# Bulb.net
KiCad netlist of a schematic drawn in Altium Designer
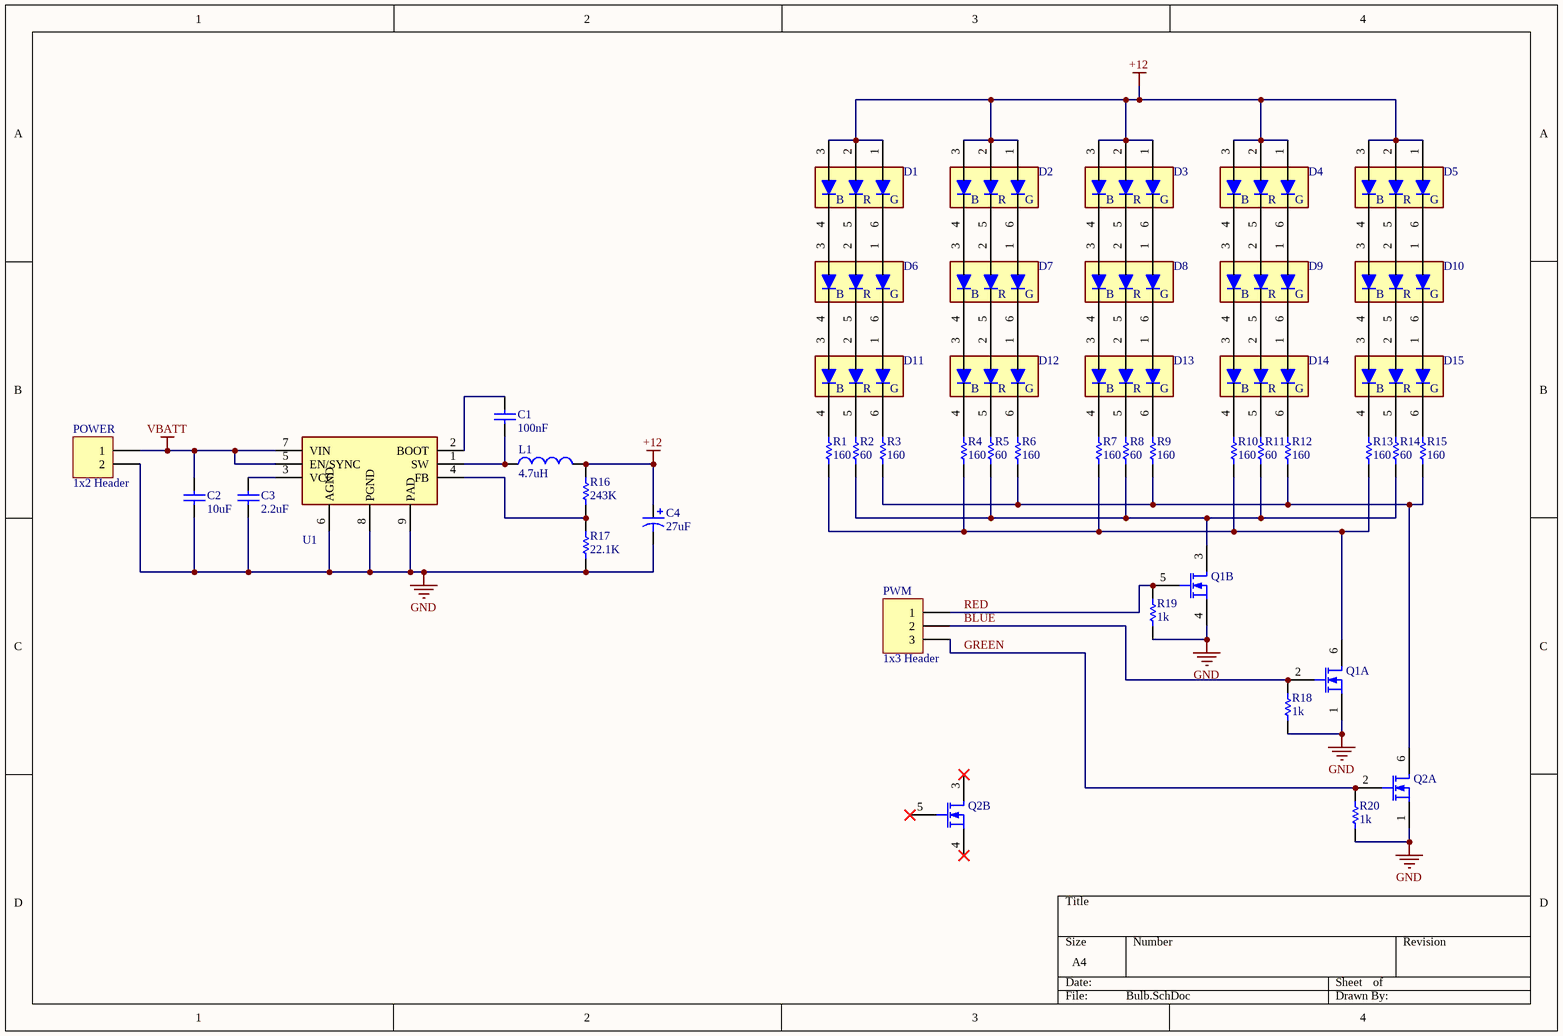
[diagram p0: Bulb.SchDoc]

(export (version "E")
  (design (tool "Eeschema 10.0.6"))
  (components
    (comp (ref "C1")
      (value "100nF")
      (footprint "0603 - Capacitor")
      (description "Nonpolarized Capacitor")
      (fields
        (field (name "MANUFACTURER") "Murata")
        (field (name "MANUFACTURER PART NUMBER") "GRM155R71C104KA88D")
      )
      (libsource (lib "General") (part "Capacitor - Nonpolarized"))
    )
    (comp (ref "C2")
      (value "10uF")
      (footprint "0603 - Capacitor")
      (description "Nonpolarized Capacitor")
      (fields
        (field (name "MANUFACTURER") "TDK")
        (field (name "MANUFACTURER PART NUMBER") "C3225X7R1H106M250AC")
      )
      (libsource (lib "General") (part "Capacitor - Nonpolarized"))
    )
    (comp (ref "C3")
      (value "2.2uF")
      (footprint "0603 - Capacitor")
      (description "Nonpolarized Capacitor")
      (fields
        (field (name "MANUFACTURER") "Kemet")
        (field (name "MANUFACTURER PART NUMBER") "C0603C225K8PACTU")
      )
      (libsource (lib "General") (part "Capacitor - Nonpolarized"))
    )
    (comp (ref "C4")
      (value "27uF")
      (footprint "OCVZ0606 - CAPACITOR")
      (description "Polarized Capacitor")
      (fields
        (field (name "MANUFACTURER") "Panasonic Electronic Components")
        (field (name "MANUFACTURER PART NUMBER") "EEE-FK1E270SR")
      )
      (libsource (lib "General") (part "Capacitor - Polarized"))
    )
    (comp (ref "D1")
      (value "RGB LED- Indiv")
      (footprint "RGB-6")
      (description "6-pin RGB LED")
      (fields
        (field (name "MANUFACTURER PART NUMBER") "HL-AF-5060H271BU46FU79GC-S1-THL")
        (field (name "MANUFACTURER") "Hongli Zhihui (HONGLITRONIC)")
      )
      (libsource (lib "General") (part "RGB LED- Indiv"))
    )
    (comp (ref "D2")
      (value "RGB LED- Indiv")
      (footprint "RGB-6")
      (description "6-pin RGB LED")
      (fields
        (field (name "MANUFACTURER PART NUMBER") "HL-AF-5060H271BU46FU79GC-S1-THL")
        (field (name "MANUFACTURER") "Hongli Zhihui (HONGLITRONIC)")
      )
      (libsource (lib "General") (part "RGB LED- Indiv"))
    )
    (comp (ref "D3")
      (value "RGB LED- Indiv")
      (footprint "RGB-6")
      (description "6-pin RGB LED")
      (fields
        (field (name "MANUFACTURER PART NUMBER") "HL-AF-5060H271BU46FU79GC-S1-THL")
        (field (name "MANUFACTURER") "Hongli Zhihui (HONGLITRONIC)")
      )
      (libsource (lib "General") (part "RGB LED- Indiv"))
    )
    (comp (ref "D4")
      (value "RGB LED- Indiv")
      (footprint "RGB-6")
      (description "6-pin RGB LED")
      (fields
        (field (name "MANUFACTURER PART NUMBER") "HL-AF-5060H271BU46FU79GC-S1-THL")
        (field (name "MANUFACTURER") "Hongli Zhihui (HONGLITRONIC)")
      )
      (libsource (lib "General") (part "RGB LED- Indiv"))
    )
    (comp (ref "D5")
      (value "RGB LED- Indiv")
      (footprint "RGB-6")
      (description "6-pin RGB LED")
      (fields
        (field (name "MANUFACTURER PART NUMBER") "HL-AF-5060H271BU46FU79GC-S1-THL")
        (field (name "MANUFACTURER") "Hongli Zhihui (HONGLITRONIC)")
      )
      (libsource (lib "General") (part "RGB LED- Indiv"))
    )
    (comp (ref "D6")
      (value "RGB LED- Indiv")
      (footprint "RGB-6")
      (description "6-pin RGB LED")
      (fields
        (field (name "MANUFACTURER PART NUMBER") "HL-AF-5060H271BU46FU79GC-S1-THL")
        (field (name "MANUFACTURER") "Hongli Zhihui (HONGLITRONIC)")
      )
      (libsource (lib "General") (part "RGB LED- Indiv"))
    )
    (comp (ref "D7")
      (value "RGB LED- Indiv")
      (footprint "RGB-6")
      (description "6-pin RGB LED")
      (fields
        (field (name "MANUFACTURER PART NUMBER") "HL-AF-5060H271BU46FU79GC-S1-THL")
        (field (name "MANUFACTURER") "Hongli Zhihui (HONGLITRONIC)")
      )
      (libsource (lib "General") (part "RGB LED- Indiv"))
    )
    (comp (ref "D8")
      (value "RGB LED- Indiv")
      (footprint "RGB-6")
      (description "6-pin RGB LED")
      (fields
        (field (name "MANUFACTURER PART NUMBER") "HL-AF-5060H271BU46FU79GC-S1-THL")
        (field (name "MANUFACTURER") "Hongli Zhihui (HONGLITRONIC)")
      )
      (libsource (lib "General") (part "RGB LED- Indiv"))
    )
    (comp (ref "D9")
      (value "RGB LED- Indiv")
      (footprint "RGB-6")
      (description "6-pin RGB LED")
      (fields
        (field (name "MANUFACTURER PART NUMBER") "HL-AF-5060H271BU46FU79GC-S1-THL")
        (field (name "MANUFACTURER") "Hongli Zhihui (HONGLITRONIC)")
      )
      (libsource (lib "General") (part "RGB LED- Indiv"))
    )
    (comp (ref "D10")
      (value "RGB LED- Indiv")
      (footprint "RGB-6")
      (description "6-pin RGB LED")
      (fields
        (field (name "MANUFACTURER PART NUMBER") "HL-AF-5060H271BU46FU79GC-S1-THL")
        (field (name "MANUFACTURER") "Hongli Zhihui (HONGLITRONIC)")
      )
      (libsource (lib "General") (part "RGB LED- Indiv"))
    )
    (comp (ref "D11")
      (value "RGB LED- Indiv")
      (footprint "RGB-6")
      (description "6-pin RGB LED")
      (fields
        (field (name "MANUFACTURER PART NUMBER") "HL-AF-5060H271BU46FU79GC-S1-THL")
        (field (name "MANUFACTURER") "Hongli Zhihui (HONGLITRONIC)")
      )
      (libsource (lib "General") (part "RGB LED- Indiv"))
    )
    (comp (ref "D12")
      (value "RGB LED- Indiv")
      (footprint "RGB-6")
      (description "6-pin RGB LED")
      (fields
        (field (name "MANUFACTURER PART NUMBER") "HL-AF-5060H271BU46FU79GC-S1-THL")
        (field (name "MANUFACTURER") "Hongli Zhihui (HONGLITRONIC)")
      )
      (libsource (lib "General") (part "RGB LED- Indiv"))
    )
    (comp (ref "D13")
      (value "RGB LED- Indiv")
      (footprint "RGB-6")
      (description "6-pin RGB LED")
      (fields
        (field (name "MANUFACTURER PART NUMBER") "HL-AF-5060H271BU46FU79GC-S1-THL")
        (field (name "MANUFACTURER") "Hongli Zhihui (HONGLITRONIC)")
      )
      (libsource (lib "General") (part "RGB LED- Indiv"))
    )
    (comp (ref "D14")
      (value "RGB LED- Indiv")
      (footprint "RGB-6")
      (description "6-pin RGB LED")
      (fields
        (field (name "MANUFACTURER PART NUMBER") "HL-AF-5060H271BU46FU79GC-S1-THL")
        (field (name "MANUFACTURER") "Hongli Zhihui (HONGLITRONIC)")
      )
      (libsource (lib "General") (part "RGB LED- Indiv"))
    )
    (comp (ref "D15")
      (value "RGB LED- Indiv")
      (footprint "RGB-6")
      (description "6-pin RGB LED")
      (fields
        (field (name "MANUFACTURER PART NUMBER") "HL-AF-5060H271BU46FU79GC-S1-THL")
        (field (name "MANUFACTURER") "Hongli Zhihui (HONGLITRONIC)")
      )
      (libsource (lib "General") (part "RGB LED- Indiv"))
    )
    (comp (ref "L1")
      (value "4.7uH")
      (footprint "PA4340 - Inductor")
      (description "Inductor")
      (fields
        (field (name "MANUFACTURER PART NUMBER") "7447706047")
        (field (name "MANUFACTURER") "Würth Elektronik")
      )
      (libsource (lib "General") (part "Inductor"))
    )
    (comp (ref "POWER")
      (value "1x2 Header")
      (footprint "B2B-XH")
      (description "1x2 Pin Header")
      (libsource (lib "GeneralConnectors") (part "1x2 Header"))
    )
    (comp (ref "PWM")
      (value "1x3 Header")
      (footprint "B3B-XH")
      (description "1x3 Pin Header")
      (libsource (lib "GeneralConnectors") (part "1x3 Header"))
    )
    (comp (ref "Q1")
      (value "BSD235NH6327XTSA1")
      (footprint "BSD235NH6327XTSA1")
      (fields (field (name "MANUFACTURER") " Infineon"))
      (libsource (lib "General") (part "BSD235NH6327XTSA1"))
    )
    (comp (ref "Q2")
      (value "BSD235NH6327XTSA1")
      (footprint "BSD235NH6327XTSA1")
      (fields (field (name "MANUFACTURER") " Infineon"))
      (libsource (lib "General") (part "BSD235NH6327XTSA1"))
    )
    (comp (ref "R1")
      (value "160")
      (footprint "1206 - Resistor")
      (description "Resistor")
      (fields (field (name "MANUFACTURER PART NUMBER") "ESR18EZPJ161") (field (name "MANUFACTURER") "Yageo"))
      (libsource (lib "General") (part "Resistor"))
    )
    (comp (ref "R2")
      (value "60")
      (footprint "0603 - Resistor")
      (description "Resistor")
      (fields
        (field (name "MANUFACTURER PART NUMBER") "RC0603FR-0759RL")
        (field (name "MANUFACTURER") "Yageo")
      )
      (libsource (lib "General") (part "Resistor"))
    )
    (comp (ref "R3")
      (value "160")
      (footprint "1206 - Resistor")
      (description "Resistor")
      (fields (field (name "MANUFACTURER PART NUMBER") "ESR18EZPJ161") (field (name "MANUFACTURER") "Yageo"))
      (libsource (lib "General") (part "Resistor"))
    )
    (comp (ref "R4")
      (value "160")
      (footprint "1206 - Resistor")
      (description "Resistor")
      (fields (field (name "MANUFACTURER PART NUMBER") "ESR18EZPJ161") (field (name "MANUFACTURER") "Yageo"))
      (libsource (lib "General") (part "Resistor"))
    )
    (comp (ref "R5")
      (value "60")
      (footprint "0603 - Resistor")
      (description "Resistor")
      (fields
        (field (name "MANUFACTURER PART NUMBER") "RC0603FR-0759RL")
        (field (name "MANUFACTURER") "Yageo")
      )
      (libsource (lib "General") (part "Resistor"))
    )
    (comp (ref "R6")
      (value "160")
      (footprint "1206 - Resistor")
      (description "Resistor")
      (fields (field (name "MANUFACTURER PART NUMBER") "ESR18EZPJ161") (field (name "MANUFACTURER") "Yageo"))
      (libsource (lib "General") (part "Resistor"))
    )
    (comp (ref "R7")
      (value "160")
      (footprint "1206 - Resistor")
      (description "Resistor")
      (fields (field (name "MANUFACTURER PART NUMBER") "ESR18EZPJ161") (field (name "MANUFACTURER") "Yageo"))
      (libsource (lib "General") (part "Resistor"))
    )
    (comp (ref "R8")
      (value "60")
      (footprint "0603 - Resistor")
      (description "Resistor")
      (fields
        (field (name "MANUFACTURER PART NUMBER") "RC0603FR-0759RL")
        (field (name "MANUFACTURER") "Yageo")
      )
      (libsource (lib "General") (part "Resistor"))
    )
    (comp (ref "R9")
      (value "160")
      (footprint "1206 - Resistor")
      (description "Resistor")
      (fields (field (name "MANUFACTURER PART NUMBER") "ESR18EZPJ161") (field (name "MANUFACTURER") "Yageo"))
      (libsource (lib "General") (part "Resistor"))
    )
    (comp (ref "R10")
      (value "160")
      (footprint "1206 - Resistor")
      (description "Resistor")
      (fields (field (name "MANUFACTURER PART NUMBER") "ESR18EZPJ161") (field (name "MANUFACTURER") "Yageo"))
      (libsource (lib "General") (part "Resistor"))
    )
    (comp (ref "R11")
      (value "60")
      (footprint "0603 - Resistor")
      (description "Resistor")
      (fields
        (field (name "MANUFACTURER PART NUMBER") "RC0603FR-0759RL")
        (field (name "MANUFACTURER") "Yageo")
      )
      (libsource (lib "General") (part "Resistor"))
    )
    (comp (ref "R12")
      (value "160")
      (footprint "1206 - Resistor")
      (description "Resistor")
      (fields (field (name "MANUFACTURER PART NUMBER") "ESR18EZPJ161") (field (name "MANUFACTURER") "Yageo"))
      (libsource (lib "General") (part "Resistor"))
    )
    (comp (ref "R13")
      (value "160")
      (footprint "1206 - Resistor")
      (description "Resistor")
      (fields (field (name "MANUFACTURER PART NUMBER") "ESR18EZPJ161") (field (name "MANUFACTURER") "Yageo"))
      (libsource (lib "General") (part "Resistor"))
    )
    (comp (ref "R14")
      (value "60")
      (footprint "0603 - Resistor")
      (description "Resistor")
      (fields
        (field (name "MANUFACTURER PART NUMBER") "RC0603FR-0759RL")
        (field (name "MANUFACTURER") "Yageo")
      )
      (libsource (lib "General") (part "Resistor"))
    )
    (comp (ref "R15")
      (value "160")
      (footprint "1206 - Resistor")
      (description "Resistor")
      (fields (field (name "MANUFACTURER PART NUMBER") "ESR18EZPJ161") (field (name "MANUFACTURER") "Yageo"))
      (libsource (lib "General") (part "Resistor"))
    )
    (comp (ref "R16")
      (value "243K")
      (footprint "0603 - Resistor")
      (description "Resistor")
      (fields
        (field (name "MANUFACTURER PART NUMBER") "RC0603FR-07243RL")
        (field (name "MANUFACTURER") "Yageo")
      )
      (libsource (lib "General") (part "Resistor"))
    )
    (comp (ref "R17")
      (value "22.1K")
      (footprint "0603 - Resistor")
      (description "Resistor")
      (fields
        (field (name "MANUFACTURER PART NUMBER") "RC0603FR-0722RL")
        (field (name "MANUFACTURER") "Yageo")
      )
      (libsource (lib "General") (part "Resistor"))
    )
    (comp (ref "R18")
      (value "1k")
      (footprint "1206 - Resistor")
      (description "Resistor")
      (fields
        (field (name "MANUFACTURER PART NUMBER") "RC0603FR-071KL")
        (field (name "MANUFACTURER") "Yageo")
      )
      (libsource (lib "General") (part "Resistor"))
    )
    (comp (ref "R19")
      (value "1k")
      (footprint "1206 - Resistor")
      (description "Resistor")
      (fields
        (field (name "MANUFACTURER PART NUMBER") "RC0603FR-071KL")
        (field (name "MANUFACTURER") "Yageo")
      )
      (libsource (lib "General") (part "Resistor"))
    )
    (comp (ref "R20")
      (value "1k")
      (footprint "1206 - Resistor")
      (description "Resistor")
      (fields
        (field (name "MANUFACTURER PART NUMBER") "RC0603FR-071KL")
        (field (name "MANUFACTURER") "Yageo")
      )
      (libsource (lib "General") (part "Resistor"))
    )
    (comp (ref "U1")
      (value "LMR23625CDDAR")
      (footprint "LMR23625CDDAR")
      (description "36V 2.5A Buck Converter")
      (fields (field (name "MANUFACTURER") "TI"))
      (libsource (lib "Embedded") (part "LMR23625CDDAR"))
    )
  )
  (nets
    (net (code "1") (name "+12") (class "Default")
      (node (ref "C4") (pin "1") (pinfunction "1_1") (pintype "passive"))
      (node (ref "D1") (pin "1") (pinfunction "11_1") (pintype "passive"))
      (node (ref "D1") (pin "2") (pinfunction "11_2") (pintype "passive"))
      (node (ref "D1") (pin "3") (pinfunction "11_3") (pintype "passive"))
      (node (ref "D2") (pin "1") (pinfunction "11_1") (pintype "passive"))
      (node (ref "D2") (pin "2") (pinfunction "11_2") (pintype "passive"))
      (node (ref "D2") (pin "3") (pinfunction "11_3") (pintype "passive"))
      (node (ref "D3") (pin "1") (pinfunction "11_1") (pintype "passive"))
      (node (ref "D3") (pin "2") (pinfunction "11_2") (pintype "passive"))
      (node (ref "D3") (pin "3") (pinfunction "11_3") (pintype "passive"))
      (node (ref "D4") (pin "1") (pinfunction "11_1") (pintype "passive"))
      (node (ref "D4") (pin "2") (pinfunction "11_2") (pintype "passive"))
      (node (ref "D4") (pin "3") (pinfunction "11_3") (pintype "passive"))
      (node (ref "D5") (pin "1") (pinfunction "11_1") (pintype "passive"))
      (node (ref "D5") (pin "2") (pinfunction "11_2") (pintype "passive"))
      (node (ref "D5") (pin "3") (pinfunction "11_3") (pintype "passive"))
      (node (ref "L1") (pin "2") (pinfunction "2_2") (pintype "passive"))
      (node (ref "R16") (pin "2") (pinfunction "2_2") (pintype "passive"))
    )
    (net (code "2") (name "/BLUE") (class "Default")
      (node (ref "PWM") (pin "2") (pinfunction "2_2") (pintype "passive"))
      (node (ref "Q1") (pin "2") (pinfunction "G_2") (pintype "passive"))
      (node (ref "R18") (pin "2") (pinfunction "2_2") (pintype "passive"))
    )
    (net (code "3") (name "/GREEN") (class "Default")
      (node (ref "PWM") (pin "3") (pinfunction "3_3") (pintype "passive"))
      (node (ref "Q2") (pin "2") (pinfunction "G_2") (pintype "passive"))
      (node (ref "R20") (pin "2") (pinfunction "2_2") (pintype "passive"))
    )
    (net (code "4") (name "/RED") (class "Default")
      (node (ref "PWM") (pin "1") (pinfunction "1_1") (pintype "passive"))
      (node (ref "Q1") (pin "5") (pinfunction "G_5") (pintype "passive"))
      (node (ref "R19") (pin "2") (pinfunction "2_2") (pintype "passive"))
    )
    (net (code "5") (name "GND") (class "Default")
      (node (ref "C2") (pin "1") (pinfunction "1_1") (pintype "passive"))
      (node (ref "C3") (pin "1") (pinfunction "1_1") (pintype "passive"))
      (node (ref "C4") (pin "2") (pinfunction "2_2") (pintype "passive"))
      (node (ref "POWER") (pin "2") (pinfunction "2_2") (pintype "passive"))
      (node (ref "Q1") (pin "1") (pinfunction "S_1") (pintype "passive"))
      (node (ref "Q1") (pin "4") (pinfunction "S_4") (pintype "passive"))
      (node (ref "Q2") (pin "1") (pinfunction "S_1") (pintype "passive"))
      (node (ref "R17") (pin "1") (pinfunction "1_1") (pintype "passive"))
      (node (ref "R18") (pin "1") (pinfunction "1_1") (pintype "passive"))
      (node (ref "R19") (pin "1") (pinfunction "1_1") (pintype "passive"))
      (node (ref "R20") (pin "1") (pinfunction "1_1") (pintype "passive"))
      (node (ref "U1") (pin "6") (pinfunction "AGND_6") (pintype "passive"))
      (node (ref "U1") (pin "8") (pinfunction "PGND_8") (pintype "passive"))
      (node (ref "U1") (pin "9") (pinfunction "PAD_9") (pintype "passive"))
    )
    (net (code "6") (name "Net-(D1-11-Pad4)") (class "Default")
      (node (ref "D1") (pin "4") (pinfunction "11_4") (pintype "passive"))
      (node (ref "D6") (pin "3") (pinfunction "11_3") (pintype "passive"))
    )
    (net (code "7") (name "Net-(D1-Pad5)") (class "Default")
      (node (ref "D1") (pin "5") (pinfunction "5_5") (pintype "passive"))
      (node (ref "D6") (pin "2") (pinfunction "11_2") (pintype "passive"))
    )
    (net (code "8") (name "Net-(D1-Pad6)") (class "Default")
      (node (ref "D1") (pin "6") (pinfunction "6_6") (pintype "passive"))
      (node (ref "D6") (pin "1") (pinfunction "11_1") (pintype "passive"))
    )
    (net (code "9") (name "Net-(D2-11-Pad4)") (class "Default")
      (node (ref "D2") (pin "4") (pinfunction "11_4") (pintype "passive"))
      (node (ref "D7") (pin "3") (pinfunction "11_3") (pintype "passive"))
    )
    (net (code "10") (name "Net-(D2-Pad5)") (class "Default")
      (node (ref "D2") (pin "5") (pinfunction "5_5") (pintype "passive"))
      (node (ref "D7") (pin "2") (pinfunction "11_2") (pintype "passive"))
    )
    (net (code "11") (name "Net-(D2-Pad6)") (class "Default")
      (node (ref "D2") (pin "6") (pinfunction "6_6") (pintype "passive"))
      (node (ref "D7") (pin "1") (pinfunction "11_1") (pintype "passive"))
    )
    (net (code "12") (name "Net-(D3-11-Pad4)") (class "Default")
      (node (ref "D3") (pin "4") (pinfunction "11_4") (pintype "passive"))
      (node (ref "D8") (pin "3") (pinfunction "11_3") (pintype "passive"))
    )
    (net (code "13") (name "Net-(D3-Pad5)") (class "Default")
      (node (ref "D3") (pin "5") (pinfunction "5_5") (pintype "passive"))
      (node (ref "D8") (pin "2") (pinfunction "11_2") (pintype "passive"))
    )
    (net (code "14") (name "Net-(D3-Pad6)") (class "Default")
      (node (ref "D3") (pin "6") (pinfunction "6_6") (pintype "passive"))
      (node (ref "D8") (pin "1") (pinfunction "11_1") (pintype "passive"))
    )
    (net (code "15") (name "Net-(D4-11-Pad4)") (class "Default")
      (node (ref "D4") (pin "4") (pinfunction "11_4") (pintype "passive"))
      (node (ref "D9") (pin "3") (pinfunction "11_3") (pintype "passive"))
    )
    (net (code "16") (name "Net-(D4-Pad5)") (class "Default")
      (node (ref "D4") (pin "5") (pinfunction "5_5") (pintype "passive"))
      (node (ref "D9") (pin "2") (pinfunction "11_2") (pintype "passive"))
    )
    (net (code "17") (name "Net-(D4-Pad6)") (class "Default")
      (node (ref "D4") (pin "6") (pinfunction "6_6") (pintype "passive"))
      (node (ref "D9") (pin "1") (pinfunction "11_1") (pintype "passive"))
    )
    (net (code "18") (name "Net-(D10-11-Pad1)") (class "Default")
      (node (ref "D10") (pin "1") (pinfunction "11_1") (pintype "passive"))
      (node (ref "D5") (pin "6") (pinfunction "6_6") (pintype "passive"))
    )
    (net (code "19") (name "Net-(D10-11-Pad2)") (class "Default")
      (node (ref "D10") (pin "2") (pinfunction "11_2") (pintype "passive"))
      (node (ref "D5") (pin "5") (pinfunction "5_5") (pintype "passive"))
    )
    (net (code "20") (name "Net-(D10-11-Pad3)") (class "Default")
      (node (ref "D10") (pin "3") (pinfunction "11_3") (pintype "passive"))
      (node (ref "D5") (pin "4") (pinfunction "11_4") (pintype "passive"))
    )
    (net (code "21") (name "Net-(D10-11-Pad4)") (class "Default")
      (node (ref "D10") (pin "4") (pinfunction "11_4") (pintype "passive"))
      (node (ref "D15") (pin "3") (pinfunction "11_3") (pintype "passive"))
    )
    (net (code "22") (name "Net-(D10-Pad5)") (class "Default")
      (node (ref "D10") (pin "5") (pinfunction "5_5") (pintype "passive"))
      (node (ref "D15") (pin "2") (pinfunction "11_2") (pintype "passive"))
    )
    (net (code "23") (name "Net-(D10-Pad6)") (class "Default")
      (node (ref "D10") (pin "6") (pinfunction "6_6") (pintype "passive"))
      (node (ref "D15") (pin "1") (pinfunction "11_1") (pintype "passive"))
    )
    (net (code "24") (name "Net-(D11-11-Pad1)") (class "Default")
      (node (ref "D11") (pin "1") (pinfunction "11_1") (pintype "passive"))
      (node (ref "D6") (pin "6") (pinfunction "6_6") (pintype "passive"))
    )
    (net (code "25") (name "Net-(D11-11-Pad2)") (class "Default")
      (node (ref "D11") (pin "2") (pinfunction "11_2") (pintype "passive"))
      (node (ref "D6") (pin "5") (pinfunction "5_5") (pintype "passive"))
    )
    (net (code "26") (name "Net-(D11-11-Pad3)") (class "Default")
      (node (ref "D11") (pin "3") (pinfunction "11_3") (pintype "passive"))
      (node (ref "D6") (pin "4") (pinfunction "11_4") (pintype "passive"))
    )
    (net (code "27") (name "Net-(D11-11-Pad4)") (class "Default")
      (node (ref "D11") (pin "4") (pinfunction "11_4") (pintype "passive"))
      (node (ref "R1") (pin "2") (pinfunction "2_2") (pintype "passive"))
    )
    (net (code "28") (name "Net-(D11-Pad5)") (class "Default")
      (node (ref "D11") (pin "5") (pinfunction "5_5") (pintype "passive"))
      (node (ref "R2") (pin "2") (pinfunction "2_2") (pintype "passive"))
    )
    (net (code "29") (name "Net-(D11-Pad6)") (class "Default")
      (node (ref "D11") (pin "6") (pinfunction "6_6") (pintype "passive"))
      (node (ref "R3") (pin "2") (pinfunction "2_2") (pintype "passive"))
    )
    (net (code "30") (name "Net-(D12-11-Pad1)") (class "Default")
      (node (ref "D12") (pin "1") (pinfunction "11_1") (pintype "passive"))
      (node (ref "D7") (pin "6") (pinfunction "6_6") (pintype "passive"))
    )
    (net (code "31") (name "Net-(D12-11-Pad2)") (class "Default")
      (node (ref "D12") (pin "2") (pinfunction "11_2") (pintype "passive"))
      (node (ref "D7") (pin "5") (pinfunction "5_5") (pintype "passive"))
    )
    (net (code "32") (name "Net-(D12-11-Pad3)") (class "Default")
      (node (ref "D12") (pin "3") (pinfunction "11_3") (pintype "passive"))
      (node (ref "D7") (pin "4") (pinfunction "11_4") (pintype "passive"))
    )
    (net (code "33") (name "Net-(D12-11-Pad4)") (class "Default")
      (node (ref "D12") (pin "4") (pinfunction "11_4") (pintype "passive"))
      (node (ref "R4") (pin "2") (pinfunction "2_2") (pintype "passive"))
    )
    (net (code "34") (name "Net-(D12-Pad5)") (class "Default")
      (node (ref "D12") (pin "5") (pinfunction "5_5") (pintype "passive"))
      (node (ref "R5") (pin "2") (pinfunction "2_2") (pintype "passive"))
    )
    (net (code "35") (name "Net-(D12-Pad6)") (class "Default")
      (node (ref "D12") (pin "6") (pinfunction "6_6") (pintype "passive"))
      (node (ref "R6") (pin "2") (pinfunction "2_2") (pintype "passive"))
    )
    (net (code "36") (name "Net-(D13-11-Pad1)") (class "Default")
      (node (ref "D13") (pin "1") (pinfunction "11_1") (pintype "passive"))
      (node (ref "D8") (pin "6") (pinfunction "6_6") (pintype "passive"))
    )
    (net (code "37") (name "Net-(D13-11-Pad2)") (class "Default")
      (node (ref "D13") (pin "2") (pinfunction "11_2") (pintype "passive"))
      (node (ref "D8") (pin "5") (pinfunction "5_5") (pintype "passive"))
    )
    (net (code "38") (name "Net-(D13-11-Pad3)") (class "Default")
      (node (ref "D13") (pin "3") (pinfunction "11_3") (pintype "passive"))
      (node (ref "D8") (pin "4") (pinfunction "11_4") (pintype "passive"))
    )
    (net (code "39") (name "Net-(D13-11-Pad4)") (class "Default")
      (node (ref "D13") (pin "4") (pinfunction "11_4") (pintype "passive"))
      (node (ref "R7") (pin "2") (pinfunction "2_2") (pintype "passive"))
    )
    (net (code "40") (name "Net-(D13-Pad5)") (class "Default")
      (node (ref "D13") (pin "5") (pinfunction "5_5") (pintype "passive"))
      (node (ref "R8") (pin "2") (pinfunction "2_2") (pintype "passive"))
    )
    (net (code "41") (name "Net-(D13-Pad6)") (class "Default")
      (node (ref "D13") (pin "6") (pinfunction "6_6") (pintype "passive"))
      (node (ref "R9") (pin "2") (pinfunction "2_2") (pintype "passive"))
    )
    (net (code "42") (name "Net-(D14-11-Pad1)") (class "Default")
      (node (ref "D14") (pin "1") (pinfunction "11_1") (pintype "passive"))
      (node (ref "D9") (pin "6") (pinfunction "6_6") (pintype "passive"))
    )
    (net (code "43") (name "Net-(D14-11-Pad2)") (class "Default")
      (node (ref "D14") (pin "2") (pinfunction "11_2") (pintype "passive"))
      (node (ref "D9") (pin "5") (pinfunction "5_5") (pintype "passive"))
    )
    (net (code "44") (name "Net-(D14-11-Pad3)") (class "Default")
      (node (ref "D14") (pin "3") (pinfunction "11_3") (pintype "passive"))
      (node (ref "D9") (pin "4") (pinfunction "11_4") (pintype "passive"))
    )
    (net (code "45") (name "Net-(D14-11-Pad4)") (class "Default")
      (node (ref "D14") (pin "4") (pinfunction "11_4") (pintype "passive"))
      (node (ref "R10") (pin "2") (pinfunction "2_2") (pintype "passive"))
    )
    (net (code "46") (name "Net-(D14-Pad5)") (class "Default")
      (node (ref "D14") (pin "5") (pinfunction "5_5") (pintype "passive"))
      (node (ref "R11") (pin "2") (pinfunction "2_2") (pintype "passive"))
    )
    (net (code "47") (name "Net-(D14-Pad6)") (class "Default")
      (node (ref "D14") (pin "6") (pinfunction "6_6") (pintype "passive"))
      (node (ref "R12") (pin "2") (pinfunction "2_2") (pintype "passive"))
    )
    (net (code "48") (name "Net-(D15-11-Pad4)") (class "Default")
      (node (ref "D15") (pin "4") (pinfunction "11_4") (pintype "passive"))
      (node (ref "R13") (pin "2") (pinfunction "2_2") (pintype "passive"))
    )
    (net (code "49") (name "Net-(D15-Pad5)") (class "Default")
      (node (ref "D15") (pin "5") (pinfunction "5_5") (pintype "passive"))
      (node (ref "R14") (pin "2") (pinfunction "2_2") (pintype "passive"))
    )
    (net (code "50") (name "Net-(D15-Pad6)") (class "Default")
      (node (ref "D15") (pin "6") (pinfunction "6_6") (pintype "passive"))
      (node (ref "R15") (pin "2") (pinfunction "2_2") (pintype "passive"))
    )
    (net (code "51") (name "Net-(Q1A-D)") (class "Default")
      (node (ref "Q1") (pin "6") (pinfunction "D_6") (pintype "passive"))
      (node (ref "R1") (pin "1") (pinfunction "1_1") (pintype "passive"))
      (node (ref "R10") (pin "1") (pinfunction "1_1") (pintype "passive"))
      (node (ref "R13") (pin "1") (pinfunction "1_1") (pintype "passive"))
      (node (ref "R4") (pin "1") (pinfunction "1_1") (pintype "passive"))
      (node (ref "R7") (pin "1") (pinfunction "1_1") (pintype "passive"))
    )
    (net (code "52") (name "Net-(Q1B-D)") (class "Default")
      (node (ref "Q1") (pin "3") (pinfunction "D_3") (pintype "passive"))
      (node (ref "R11") (pin "1") (pinfunction "1_1") (pintype "passive"))
      (node (ref "R14") (pin "1") (pinfunction "1_1") (pintype "passive"))
      (node (ref "R2") (pin "1") (pinfunction "1_1") (pintype "passive"))
      (node (ref "R5") (pin "1") (pinfunction "1_1") (pintype "passive"))
      (node (ref "R8") (pin "1") (pinfunction "1_1") (pintype "passive"))
    )
    (net (code "53") (name "Net-(Q2A-D)") (class "Default")
      (node (ref "Q2") (pin "6") (pinfunction "D_6") (pintype "passive"))
      (node (ref "R12") (pin "1") (pinfunction "1_1") (pintype "passive"))
      (node (ref "R15") (pin "1") (pinfunction "1_1") (pintype "passive"))
      (node (ref "R3") (pin "1") (pinfunction "1_1") (pintype "passive"))
      (node (ref "R6") (pin "1") (pinfunction "1_1") (pintype "passive"))
      (node (ref "R9") (pin "1") (pinfunction "1_1") (pintype "passive"))
    )
    (net (code "54") (name "Net-(U1-BOOT)") (class "Default")
      (node (ref "C1") (pin "2") (pinfunction "2_2") (pintype "passive"))
      (node (ref "U1") (pin "2") (pinfunction "BOOT_2") (pintype "passive"))
    )
    (net (code "55") (name "Net-(U1-FB)") (class "Default")
      (node (ref "R16") (pin "1") (pinfunction "1_1") (pintype "passive"))
      (node (ref "R17") (pin "2") (pinfunction "2_2") (pintype "passive"))
      (node (ref "U1") (pin "4") (pinfunction "FB_4") (pintype "passive"))
    )
    (net (code "56") (name "Net-(U1-SW)") (class "Default")
      (node (ref "C1") (pin "1") (pinfunction "1_1") (pintype "passive"))
      (node (ref "L1") (pin "1") (pinfunction "1_1") (pintype "passive"))
      (node (ref "U1") (pin "1") (pinfunction "SW_1") (pintype "passive"))
    )
    (net (code "57") (name "Net-(U1-VCC)") (class "Default")
      (node (ref "C3") (pin "2") (pinfunction "2_2") (pintype "passive"))
      (node (ref "U1") (pin "3") (pinfunction "VCC_3") (pintype "passive"))
    )
    (net (code "58") (name "VBATT") (class "Default")
      (node (ref "C2") (pin "2") (pinfunction "2_2") (pintype "passive"))
      (node (ref "POWER") (pin "1") (pinfunction "1_1") (pintype "passive"))
      (node (ref "U1") (pin "5") (pinfunction "EN/SYNC_5") (pintype "passive"))
      (node (ref "U1") (pin "7") (pinfunction "VIN_7") (pintype "passive"))
    )
    (net (code "59") (name "unconnected-(Q2B-D-Pad3)") (class "Default")
      (node (ref "Q2") (pin "3") (pinfunction "D_3") (pintype "passive+no_connect"))
    )
    (net (code "60") (name "unconnected-(Q2B-G-Pad5)") (class "Default")
      (node (ref "Q2") (pin "5") (pinfunction "G_5") (pintype "passive+no_connect"))
    )
    (net (code "61") (name "unconnected-(Q2B-S-Pad4)") (class "Default")
      (node (ref "Q2") (pin "4") (pinfunction "S_4") (pintype "passive+no_connect"))
    )
  )
)
